# DRV8302_Breakout.net
KiCad netlist of a schematic drawn in EAGLE
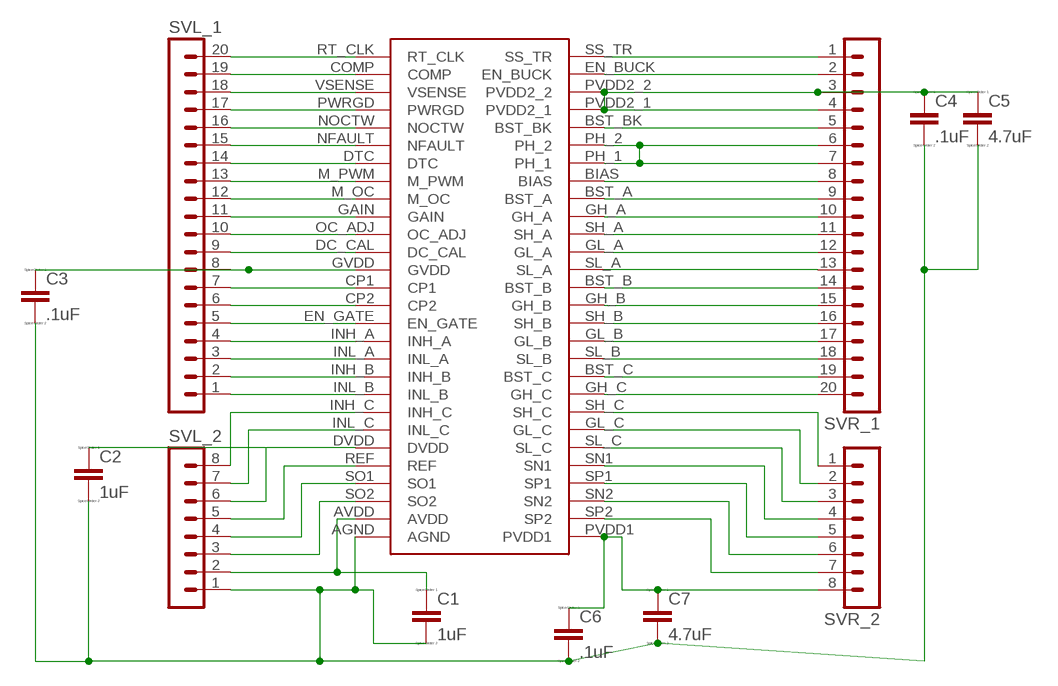
[diagram p0: schematic, sheet 1]

(export (version "E")
  (design (tool "Eeschema 10.0.6"))
  (components
    (comp (ref "C1")
      (value "1uF")
      (footprint "eagle-import:C0603")
      (libsource (lib "eagle-import") (part "CC0603"))
    )
    (comp (ref "C2")
      (value "1uF")
      (footprint "eagle-import:C0603")
      (libsource (lib "eagle-import") (part "CC0603"))
    )
    (comp (ref "C3")
      (value ".1uF")
      (footprint "eagle-import:C0603")
      (libsource (lib "eagle-import") (part "CC0603"))
    )
    (comp (ref "C4")
      (value ".1uF")
      (footprint "eagle-import:C0603")
      (libsource (lib "eagle-import") (part "CC0603"))
    )
    (comp (ref "C5")
      (value "4.7uF")
      (footprint "eagle-import:C0603")
      (libsource (lib "eagle-import") (part "CC0603"))
    )
    (comp (ref "C6")
      (value ".1uF")
      (footprint "eagle-import:C0603")
      (libsource (lib "eagle-import") (part "CC0603"))
    )
    (comp (ref "C7")
      (value "4.7uF")
      (footprint "eagle-import:C0603")
      (libsource (lib "eagle-import") (part "CC0603"))
    )
    (comp (ref "IC1")
      (value "DRV8302DRV8302")
      (footprint "eagle-import:DRV8302")
      (libsource (lib "eagle-import") (part "DRV8302DRV8302"))
    )
    (comp (ref "SVL_1")
      (value "MA20-1")
      (footprint "eagle-import:MA20-1")
      (libsource (lib "eagle-import") (part "MA20-1"))
    )
    (comp (ref "SVL_2")
      (value "MA08-1")
      (footprint "eagle-import:MA08-1")
      (libsource (lib "eagle-import") (part "MA08-1"))
    )
    (comp (ref "SVR_1")
      (value "MA20-1")
      (footprint "eagle-import:MA20-1")
      (libsource (lib "eagle-import") (part "MA20-1"))
    )
    (comp (ref "SVR_2")
      (value "MA08-1")
      (footprint "eagle-import:MA08-1")
      (libsource (lib "eagle-import") (part "MA08-1"))
    )
  )
  (nets
    (net (code "1") (name "Net-(C1-Pad1)") (class "Default")
      (node (ref "C1") (pin "1") (pinfunction "1_1") (pintype "passive"))
      (node (ref "IC1") (pin "AVDD") (pinfunction "AVDD_AVDD") (pintype "bidirectional"))
      (node (ref "SVL_2") (pin "2") (pinfunction "2_2") (pintype "passive"))
    )
    (net (code "2") (name "Net-(C1-Pad2)") (class "Default")
      (node (ref "C1") (pin "2") (pinfunction "2_2") (pintype "passive"))
      (node (ref "C2") (pin "2") (pinfunction "2_2") (pintype "passive"))
      (node (ref "C3") (pin "2") (pinfunction "2_2") (pintype "passive"))
      (node (ref "C4") (pin "2") (pinfunction "2_2") (pintype "passive"))
      (node (ref "C5") (pin "2") (pinfunction "2_2") (pintype "passive"))
      (node (ref "C6") (pin "2") (pinfunction "2_2") (pintype "passive"))
      (node (ref "C7") (pin "2") (pinfunction "2_2") (pintype "passive"))
      (node (ref "IC1") (pin "AGND") (pinfunction "AGND_AGND") (pintype "bidirectional"))
      (node (ref "SVL_2") (pin "1") (pinfunction "1_1") (pintype "passive"))
    )
    (net (code "3") (name "Net-(C2-Pad1)") (class "Default")
      (node (ref "C2") (pin "1") (pinfunction "1_1") (pintype "passive"))
      (node (ref "IC1") (pin "DVDD") (pinfunction "DVDD_DVDD") (pintype "bidirectional"))
      (node (ref "SVL_2") (pin "6") (pinfunction "6_6") (pintype "passive"))
    )
    (net (code "4") (name "Net-(C3-Pad1)") (class "Default")
      (node (ref "C3") (pin "1") (pinfunction "1_1") (pintype "passive"))
      (node (ref "IC1") (pin "GVDD") (pinfunction "GVDD_GVDD") (pintype "bidirectional"))
      (node (ref "SVL_1") (pin "8") (pinfunction "8_8") (pintype "passive"))
    )
    (net (code "5") (name "Net-(C4-Pad1)") (class "Default")
      (node (ref "C4") (pin "1") (pinfunction "1_1") (pintype "passive"))
      (node (ref "C5") (pin "1") (pinfunction "1_1") (pintype "passive"))
      (node (ref "IC1") (pin "PVDD2_1") (pinfunction "PVDD2_1_PVDD2_1") (pintype "bidirectional"))
      (node (ref "IC1") (pin "PVDD2_2") (pinfunction "PVDD2_2_PVDD2_2") (pintype "bidirectional"))
      (node (ref "SVR_1") (pin "3") (pinfunction "3_3") (pintype "passive"))
      (node (ref "SVR_1") (pin "4") (pinfunction "4_4") (pintype "passive"))
    )
    (net (code "6") (name "Net-(C6-Pad1)") (class "Default")
      (node (ref "C6") (pin "1") (pinfunction "1_1") (pintype "passive"))
      (node (ref "C7") (pin "1") (pinfunction "1_1") (pintype "passive"))
      (node (ref "IC1") (pin "PVDD1") (pinfunction "PVDD1_PVDD1") (pintype "bidirectional"))
      (node (ref "SVR_2") (pin "8") (pinfunction "8_8") (pintype "passive"))
    )
    (net (code "7") (name "Net-(IC1-PadBIAS)") (class "Default")
      (node (ref "IC1") (pin "BIAS") (pinfunction "BIAS_BIAS") (pintype "bidirectional"))
      (node (ref "SVR_1") (pin "8") (pinfunction "8_8") (pintype "passive"))
    )
    (net (code "8") (name "Net-(IC1-PadBST_A)") (class "Default")
      (node (ref "IC1") (pin "BST_A") (pinfunction "BST_A_BST_A") (pintype "bidirectional"))
      (node (ref "SVR_1") (pin "9") (pinfunction "9_9") (pintype "passive"))
    )
    (net (code "9") (name "Net-(IC1-PadBST_B)") (class "Default")
      (node (ref "IC1") (pin "BST_B") (pinfunction "BST_B_BST_B") (pintype "bidirectional"))
      (node (ref "SVR_1") (pin "14") (pinfunction "14_14") (pintype "passive"))
    )
    (net (code "10") (name "Net-(IC1-PadBST_BK)") (class "Default")
      (node (ref "IC1") (pin "BST_BK") (pinfunction "BST_BK_BST_BK") (pintype "bidirectional"))
      (node (ref "SVR_1") (pin "5") (pinfunction "5_5") (pintype "passive"))
    )
    (net (code "11") (name "Net-(IC1-PadBST_C)") (class "Default")
      (node (ref "IC1") (pin "BST_C") (pinfunction "BST_C_BST_C") (pintype "bidirectional"))
      (node (ref "SVR_1") (pin "19") (pinfunction "19_19") (pintype "passive"))
    )
    (net (code "12") (name "Net-(IC1-PadCOMP)") (class "Default")
      (node (ref "IC1") (pin "COMP") (pinfunction "COMP_COMP") (pintype "bidirectional"))
      (node (ref "SVL_1") (pin "19") (pinfunction "19_19") (pintype "passive"))
    )
    (net (code "13") (name "Net-(IC1-PadCP1)") (class "Default")
      (node (ref "IC1") (pin "CP1") (pinfunction "CP1_CP1") (pintype "bidirectional"))
      (node (ref "SVL_1") (pin "7") (pinfunction "7_7") (pintype "passive"))
    )
    (net (code "14") (name "Net-(IC1-PadCP2)") (class "Default")
      (node (ref "IC1") (pin "CP2") (pinfunction "CP2_CP2") (pintype "bidirectional"))
      (node (ref "SVL_1") (pin "6") (pinfunction "6_6") (pintype "passive"))
    )
    (net (code "15") (name "Net-(IC1-PadDC_CAL)") (class "Default")
      (node (ref "IC1") (pin "DC_CAL") (pinfunction "DC_CAL_DC_CAL") (pintype "bidirectional"))
      (node (ref "SVL_1") (pin "9") (pinfunction "9_9") (pintype "passive"))
    )
    (net (code "16") (name "Net-(IC1-PadDTC)") (class "Default")
      (node (ref "IC1") (pin "DTC") (pinfunction "DTC_DTC") (pintype "bidirectional"))
      (node (ref "SVL_1") (pin "14") (pinfunction "14_14") (pintype "passive"))
    )
    (net (code "17") (name "Net-(IC1-PadEN_BUCK)") (class "Default")
      (node (ref "IC1") (pin "EN_BUCK") (pinfunction "EN_BUCK_EN_BUCK") (pintype "bidirectional"))
      (node (ref "SVR_1") (pin "2") (pinfunction "2_2") (pintype "passive"))
    )
    (net (code "18") (name "Net-(IC1-PadEN_GATE)") (class "Default")
      (node (ref "IC1") (pin "EN_GATE") (pinfunction "EN_GATE_EN_GATE") (pintype "bidirectional"))
      (node (ref "SVL_1") (pin "5") (pinfunction "5_5") (pintype "passive"))
    )
    (net (code "19") (name "Net-(IC1-PadGAIN)") (class "Default")
      (node (ref "IC1") (pin "GAIN") (pinfunction "GAIN_GAIN") (pintype "bidirectional"))
      (node (ref "SVL_1") (pin "11") (pinfunction "11_11") (pintype "passive"))
    )
    (net (code "20") (name "Net-(IC1-PadGH_A)") (class "Default")
      (node (ref "IC1") (pin "GH_A") (pinfunction "GH_A_GH_A") (pintype "bidirectional"))
      (node (ref "SVR_1") (pin "10") (pinfunction "10_10") (pintype "passive"))
    )
    (net (code "21") (name "Net-(IC1-PadGH_B)") (class "Default")
      (node (ref "IC1") (pin "GH_B") (pinfunction "GH_B_GH_B") (pintype "bidirectional"))
      (node (ref "SVR_1") (pin "15") (pinfunction "15_15") (pintype "passive"))
    )
    (net (code "22") (name "Net-(IC1-PadGH_C)") (class "Default")
      (node (ref "IC1") (pin "GH_C") (pinfunction "GH_C_GH_C") (pintype "bidirectional"))
      (node (ref "SVR_1") (pin "20") (pinfunction "20_20") (pintype "passive"))
    )
    (net (code "23") (name "Net-(IC1-PadGL_A)") (class "Default")
      (node (ref "IC1") (pin "GL_A") (pinfunction "GL_A_GL_A") (pintype "bidirectional"))
      (node (ref "SVR_1") (pin "12") (pinfunction "12_12") (pintype "passive"))
    )
    (net (code "24") (name "Net-(IC1-PadGL_B)") (class "Default")
      (node (ref "IC1") (pin "GL_B") (pinfunction "GL_B_GL_B") (pintype "bidirectional"))
      (node (ref "SVR_1") (pin "17") (pinfunction "17_17") (pintype "passive"))
    )
    (net (code "25") (name "Net-(IC1-PadGL_C)") (class "Default")
      (node (ref "IC1") (pin "GL_C") (pinfunction "GL_C_GL_C") (pintype "bidirectional"))
      (node (ref "SVR_2") (pin "2") (pinfunction "2_2") (pintype "passive"))
    )
    (net (code "26") (name "Net-(IC1-PadINH_A)") (class "Default")
      (node (ref "IC1") (pin "INH_A") (pinfunction "INH_A_INH_A") (pintype "bidirectional"))
      (node (ref "SVL_1") (pin "4") (pinfunction "4_4") (pintype "passive"))
    )
    (net (code "27") (name "Net-(IC1-PadINH_B)") (class "Default")
      (node (ref "IC1") (pin "INH_B") (pinfunction "INH_B_INH_B") (pintype "bidirectional"))
      (node (ref "SVL_1") (pin "2") (pinfunction "2_2") (pintype "passive"))
    )
    (net (code "28") (name "Net-(IC1-PadINH_C)") (class "Default")
      (node (ref "IC1") (pin "INH_C") (pinfunction "INH_C_INH_C") (pintype "bidirectional"))
      (node (ref "SVL_2") (pin "8") (pinfunction "8_8") (pintype "passive"))
    )
    (net (code "29") (name "Net-(IC1-PadINL_A)") (class "Default")
      (node (ref "IC1") (pin "INL_A") (pinfunction "INL_A_INL_A") (pintype "bidirectional"))
      (node (ref "SVL_1") (pin "3") (pinfunction "3_3") (pintype "passive"))
    )
    (net (code "30") (name "Net-(IC1-PadINL_B)") (class "Default")
      (node (ref "IC1") (pin "INL_B") (pinfunction "INL_B_INL_B") (pintype "bidirectional"))
      (node (ref "SVL_1") (pin "1") (pinfunction "1_1") (pintype "passive"))
    )
    (net (code "31") (name "Net-(IC1-PadINL_C)") (class "Default")
      (node (ref "IC1") (pin "INL_C") (pinfunction "INL_C_INL_C") (pintype "bidirectional"))
      (node (ref "SVL_2") (pin "7") (pinfunction "7_7") (pintype "passive"))
    )
    (net (code "32") (name "Net-(IC1-PadM_OC)") (class "Default")
      (node (ref "IC1") (pin "M_OC") (pinfunction "M_OC_M_OC") (pintype "bidirectional"))
      (node (ref "SVL_1") (pin "12") (pinfunction "12_12") (pintype "passive"))
    )
    (net (code "33") (name "Net-(IC1-PadM_PWM)") (class "Default")
      (node (ref "IC1") (pin "M_PWM") (pinfunction "M_PWM_M_PWM") (pintype "bidirectional"))
      (node (ref "SVL_1") (pin "13") (pinfunction "13_13") (pintype "passive"))
    )
    (net (code "34") (name "Net-(IC1-PadNFAULT)") (class "Default")
      (node (ref "IC1") (pin "NFAULT") (pinfunction "NFAULT_NFAULT") (pintype "bidirectional"))
      (node (ref "SVL_1") (pin "15") (pinfunction "15_15") (pintype "passive"))
    )
    (net (code "35") (name "Net-(IC1-PadNOCTW)") (class "Default")
      (node (ref "IC1") (pin "NOCTW") (pinfunction "NOCTW_NOCTW") (pintype "bidirectional"))
      (node (ref "SVL_1") (pin "16") (pinfunction "16_16") (pintype "passive"))
    )
    (net (code "36") (name "Net-(IC1-PadOC_ADJ)") (class "Default")
      (node (ref "IC1") (pin "OC_ADJ") (pinfunction "OC_ADJ_OC_ADJ") (pintype "bidirectional"))
      (node (ref "SVL_1") (pin "10") (pinfunction "10_10") (pintype "passive"))
    )
    (net (code "37") (name "Net-(IC1-PadPH_1)") (class "Default")
      (node (ref "IC1") (pin "PH_1") (pinfunction "PH_1_PH_1") (pintype "bidirectional"))
      (node (ref "IC1") (pin "PH_2") (pinfunction "PH_2_PH_2") (pintype "bidirectional"))
      (node (ref "SVR_1") (pin "6") (pinfunction "6_6") (pintype "passive"))
      (node (ref "SVR_1") (pin "7") (pinfunction "7_7") (pintype "passive"))
    )
    (net (code "38") (name "Net-(IC1-PadPWRGD)") (class "Default")
      (node (ref "IC1") (pin "PWRGD") (pinfunction "PWRGD_PWRGD") (pintype "bidirectional"))
      (node (ref "SVL_1") (pin "17") (pinfunction "17_17") (pintype "passive"))
    )
    (net (code "39") (name "Net-(IC1-PadREF)") (class "Default")
      (node (ref "IC1") (pin "REF") (pinfunction "REF_REF") (pintype "bidirectional"))
      (node (ref "SVL_2") (pin "5") (pinfunction "5_5") (pintype "passive"))
    )
    (net (code "40") (name "Net-(IC1-PadRT_CLK)") (class "Default")
      (node (ref "IC1") (pin "RT_CLK") (pinfunction "RT_CLK_RT_CLK") (pintype "bidirectional"))
      (node (ref "SVL_1") (pin "20") (pinfunction "20_20") (pintype "passive"))
    )
    (net (code "41") (name "Net-(IC1-PadSH_A)") (class "Default")
      (node (ref "IC1") (pin "SH_A") (pinfunction "SH_A_SH_A") (pintype "bidirectional"))
      (node (ref "SVR_1") (pin "11") (pinfunction "11_11") (pintype "passive"))
    )
    (net (code "42") (name "Net-(IC1-PadSH_B)") (class "Default")
      (node (ref "IC1") (pin "SH_B") (pinfunction "SH_B_SH_B") (pintype "bidirectional"))
      (node (ref "SVR_1") (pin "16") (pinfunction "16_16") (pintype "passive"))
    )
    (net (code "43") (name "Net-(IC1-PadSH_C)") (class "Default")
      (node (ref "IC1") (pin "SH_C") (pinfunction "SH_C_SH_C") (pintype "bidirectional"))
      (node (ref "SVR_2") (pin "1") (pinfunction "1_1") (pintype "passive"))
    )
    (net (code "44") (name "Net-(IC1-PadSL_A)") (class "Default")
      (node (ref "IC1") (pin "SL_A") (pinfunction "SL_A_SL_A") (pintype "bidirectional"))
      (node (ref "SVR_1") (pin "13") (pinfunction "13_13") (pintype "passive"))
    )
    (net (code "45") (name "Net-(IC1-PadSL_B)") (class "Default")
      (node (ref "IC1") (pin "SL_B") (pinfunction "SL_B_SL_B") (pintype "bidirectional"))
      (node (ref "SVR_1") (pin "18") (pinfunction "18_18") (pintype "passive"))
    )
    (net (code "46") (name "Net-(IC1-PadSL_C)") (class "Default")
      (node (ref "IC1") (pin "SL_C") (pinfunction "SL_C_SL_C") (pintype "bidirectional"))
      (node (ref "SVR_2") (pin "3") (pinfunction "3_3") (pintype "passive"))
    )
    (net (code "47") (name "Net-(IC1-PadSN1)") (class "Default")
      (node (ref "IC1") (pin "SN1") (pinfunction "SN1_SN1") (pintype "bidirectional"))
      (node (ref "SVR_2") (pin "4") (pinfunction "4_4") (pintype "passive"))
    )
    (net (code "48") (name "Net-(IC1-PadSN2)") (class "Default")
      (node (ref "IC1") (pin "SN2") (pinfunction "SN2_SN2") (pintype "bidirectional"))
      (node (ref "SVR_2") (pin "6") (pinfunction "6_6") (pintype "passive"))
    )
    (net (code "49") (name "Net-(IC1-PadSO1)") (class "Default")
      (node (ref "IC1") (pin "SO1") (pinfunction "SO1_SO1") (pintype "bidirectional"))
      (node (ref "SVL_2") (pin "4") (pinfunction "4_4") (pintype "passive"))
    )
    (net (code "50") (name "Net-(IC1-PadSO2)") (class "Default")
      (node (ref "IC1") (pin "SO2") (pinfunction "SO2_SO2") (pintype "bidirectional"))
      (node (ref "SVL_2") (pin "3") (pinfunction "3_3") (pintype "passive"))
    )
    (net (code "51") (name "Net-(IC1-PadSP1)") (class "Default")
      (node (ref "IC1") (pin "SP1") (pinfunction "SP1_SP1") (pintype "bidirectional"))
      (node (ref "SVR_2") (pin "5") (pinfunction "5_5") (pintype "passive"))
    )
    (net (code "52") (name "Net-(IC1-PadSP2)") (class "Default")
      (node (ref "IC1") (pin "SP2") (pinfunction "SP2_SP2") (pintype "bidirectional"))
      (node (ref "SVR_2") (pin "7") (pinfunction "7_7") (pintype "passive"))
    )
    (net (code "53") (name "Net-(IC1-PadSS_TR)") (class "Default")
      (node (ref "IC1") (pin "SS_TR") (pinfunction "SS_TR_SS_TR") (pintype "bidirectional"))
      (node (ref "SVR_1") (pin "1") (pinfunction "1_1") (pintype "passive"))
    )
    (net (code "54") (name "Net-(IC1-PadVSENSE)") (class "Default")
      (node (ref "IC1") (pin "VSENSE") (pinfunction "VSENSE_VSENSE") (pintype "bidirectional"))
      (node (ref "SVL_1") (pin "18") (pinfunction "18_18") (pintype "passive"))
    )
  )
)
